# Wifi.net
KiCad netlist of a schematic drawn in Altium Designer
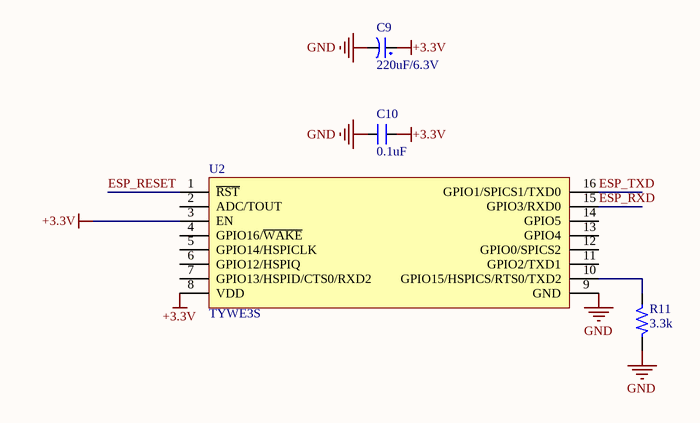
[diagram p0: Wifi.SchDoc]

(export (version "E")
  (design (tool "Eeschema 10.0.6"))
  (components
    (comp (ref "C9")
      (value "220uF/6.3V")
      (footprint "C2917")
      (description "Cap P  0,1uF < 22uF , 16 - 50V")
      (libsource (lib "nl") (part "CP1"))
    )
    (comp (ref "C10")
      (value "0.1uF")
      (footprint "C0603")
      (description "Cap SMD")
      (libsource (lib "syhaunguyen") (part "CM"))
    )
    (comp (ref "R11")
      (value "3.3k")
      (footprint "R0603")
      (description "Resistor 1/4W")
      (libsource (lib "nl") (part "R"))
    )
    (comp (ref "U2")
      (value "TYWE3S")
      (footprint "ESP_07")
      (description "ESP-12 Wi-Fi Module by AI-Thinker")
      (libsource (lib "nl") (part "ESP_07"))
    )
  )
  (nets
    (net (code "1") (name "+3.3V") (class "Default")
      (node (ref "C10") (pin "2") (pinfunction "2_2") (pintype "passive"))
      (node (ref "C9") (pin "1") (pinfunction "1_1") (pintype "passive"))
      (node (ref "U2") (pin "3") (pinfunction "EN_3") (pintype "passive"))
      (node (ref "U2") (pin "8") (pinfunction "VDD_8") (pintype "passive"))
    )
    (net (code "2") (name "/ESP_RESET") (class "Default")
      (node (ref "U2") (pin "1") (pinfunction "~{RST}_1") (pintype "passive"))
    )
    (net (code "3") (name "/ESP_RXD") (class "Default")
      (node (ref "U2") (pin "15") (pinfunction "GPIO3/RXD0_15") (pintype "passive"))
    )
    (net (code "4") (name "/ESP_TXD") (class "Default")
      (node (ref "U2") (pin "16") (pinfunction "GPIO1/SPICS1/TXD0_16") (pintype "passive"))
    )
    (net (code "5") (name "GND") (class "Default")
      (node (ref "C10") (pin "1") (pinfunction "1_1") (pintype "passive"))
      (node (ref "C9") (pin "2") (pinfunction "2_2") (pintype "passive"))
      (node (ref "R11") (pin "2") (pinfunction "2_2") (pintype "passive"))
      (node (ref "U2") (pin "9") (pinfunction "GND_9") (pintype "passive"))
    )
    (net (code "6") (name "Net-(U2-GPIO15{slash}HSPICS{slash}RTS0{slash}TXD2)") (class "Default")
      (node (ref "R11") (pin "1") (pinfunction "1_1") (pintype "passive"))
      (node (ref "U2") (pin "10") (pinfunction "GPIO15/HSPICS/RTS0/TXD2_10") (pintype "passive"))
    )
    (net (code "7") (name "unconnected-(U2-ADC{slash}TOUT-Pad2)") (class "Default")
      (node (ref "U2") (pin "2") (pinfunction "ADC/TOUT_2") (pintype "passive"))
    )
    (net (code "8") (name "unconnected-(U2-GPIO0{slash}SPICS2-Pad12)") (class "Default")
      (node (ref "U2") (pin "12") (pinfunction "GPIO0/SPICS2_12") (pintype "passive"))
    )
    (net (code "9") (name "unconnected-(U2-GPIO2{slash}TXD1-Pad11)") (class "Default")
      (node (ref "U2") (pin "11") (pinfunction "GPIO2/TXD1_11") (pintype "passive"))
    )
    (net (code "10") (name "unconnected-(U2-GPIO4-Pad13)") (class "Default")
      (node (ref "U2") (pin "13") (pinfunction "GPIO4_13") (pintype "passive"))
    )
    (net (code "11") (name "unconnected-(U2-GPIO5-Pad14)") (class "Default")
      (node (ref "U2") (pin "14") (pinfunction "GPIO5_14") (pintype "passive"))
    )
    (net (code "12") (name "unconnected-(U2-GPIO12{slash}HSPIQ-Pad6)") (class "Default")
      (node (ref "U2") (pin "6") (pinfunction "GPIO12/HSPIQ_6") (pintype "passive"))
    )
    (net (code "13") (name "unconnected-(U2-GPIO13{slash}HSPID{slash}CTS0{slash}RXD2-Pad7)") (class "Default")
      (node (ref "U2") (pin "7") (pinfunction "GPIO13/HSPID/CTS0/RXD2_7") (pintype "passive"))
    )
    (net (code "14") (name "unconnected-(U2-GPIO14{slash}HSPICLK-Pad5)") (class "Default")
      (node (ref "U2") (pin "5") (pinfunction "GPIO14/HSPICLK_5") (pintype "passive"))
    )
    (net (code "15") (name "unconnected-(U2-GPIO16{slash}~{WAKE}-Pad4)") (class "Default")
      (node (ref "U2") (pin "4") (pinfunction "GPIO16/~{WAKE}_4") (pintype "passive"))
    )
  )
)
